# HeatBedRelay5D_int.net
KiCad netlist of a schematic drawn in EAGLE
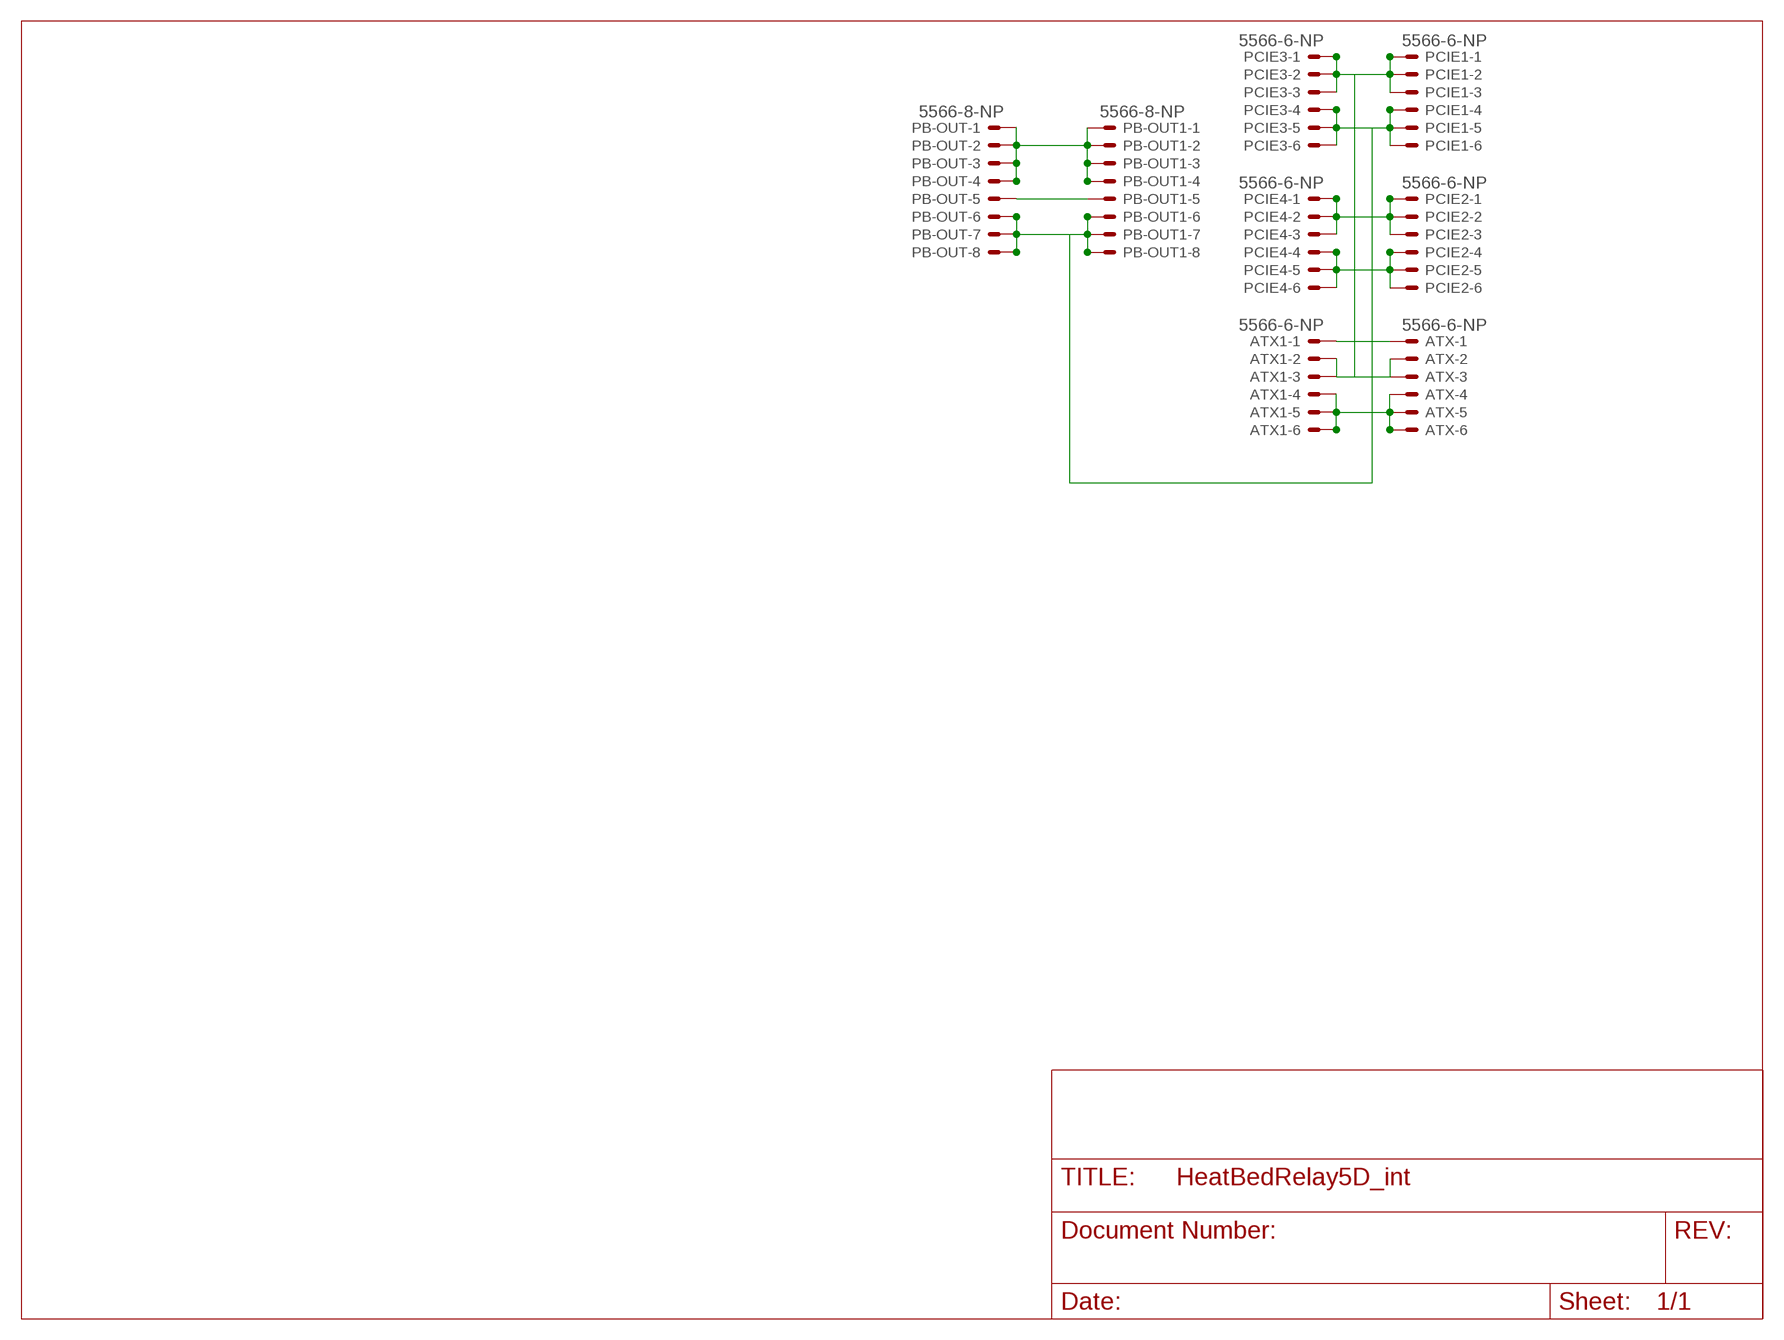
[diagram p0: schematic, sheet 1]

(export (version "E")
  (design (tool "Eeschema 10.0.6"))
  (components
    (comp (ref "ATX")
      (value "5566-6-NP")
      (footprint "eagle-import:5566-6-NP")
      (libsource (lib "eagle-import") (part "5566-6-NP"))
    )
    (comp (ref "ATX1")
      (value "5566-6-NP")
      (footprint "eagle-import:5566-6-NP")
      (libsource (lib "eagle-import") (part "5566-6-NP"))
    )
    (comp (ref "PB-OUT")
      (value "5566-8-NP")
      (footprint "eagle-import:5566-8-NP")
      (libsource (lib "eagle-import") (part "5566-8-NP"))
    )
    (comp (ref "PB-OUT1")
      (value "5566-8-NP")
      (footprint "eagle-import:5566-8-NP")
      (libsource (lib "eagle-import") (part "5566-8-NP"))
    )
    (comp (ref "PCIE1")
      (value "5566-6-NP")
      (footprint "eagle-import:5566-6-NP")
      (libsource (lib "eagle-import") (part "5566-6-NP"))
    )
    (comp (ref "PCIE2")
      (value "5566-6-NP")
      (footprint "eagle-import:5566-6-NP")
      (libsource (lib "eagle-import") (part "5566-6-NP"))
    )
    (comp (ref "PCIE3")
      (value "5566-6-NP")
      (footprint "eagle-import:5566-6-NP")
      (libsource (lib "eagle-import") (part "5566-6-NP"))
    )
    (comp (ref "PCIE4")
      (value "5566-6-NP")
      (footprint "eagle-import:5566-6-NP")
      (libsource (lib "eagle-import") (part "5566-6-NP"))
    )
  )
  (nets
    (net (code "1") (name "Net-(ATX1A-S)") (class "Default")
      (node (ref "ATX") (pin "1") (pinfunction "S_1") (pintype "passive"))
      (node (ref "ATX1") (pin "1") (pinfunction "S_1") (pintype "passive"))
    )
    (net (code "2") (name "Net-(ATX1B-S)") (class "Default")
      (node (ref "ATX") (pin "2") (pinfunction "S_2") (pintype "passive"))
      (node (ref "ATX") (pin "3") (pinfunction "S_3") (pintype "passive"))
      (node (ref "ATX1") (pin "2") (pinfunction "S_2") (pintype "passive"))
      (node (ref "ATX1") (pin "3") (pinfunction "S_3") (pintype "passive"))
      (node (ref "PCIE1") (pin "1") (pinfunction "S_1") (pintype "passive"))
      (node (ref "PCIE1") (pin "2") (pinfunction "S_2") (pintype "passive"))
      (node (ref "PCIE1") (pin "3") (pinfunction "S_3") (pintype "passive"))
      (node (ref "PCIE2") (pin "1") (pinfunction "S_1") (pintype "passive"))
      (node (ref "PCIE2") (pin "2") (pinfunction "S_2") (pintype "passive"))
      (node (ref "PCIE2") (pin "3") (pinfunction "S_3") (pintype "passive"))
      (node (ref "PCIE3") (pin "1") (pinfunction "S_1") (pintype "passive"))
      (node (ref "PCIE3") (pin "2") (pinfunction "S_2") (pintype "passive"))
      (node (ref "PCIE3") (pin "3") (pinfunction "S_3") (pintype "passive"))
      (node (ref "PCIE4") (pin "1") (pinfunction "S_1") (pintype "passive"))
      (node (ref "PCIE4") (pin "2") (pinfunction "S_2") (pintype "passive"))
      (node (ref "PCIE4") (pin "3") (pinfunction "S_3") (pintype "passive"))
    )
    (net (code "3") (name "Net-(ATX1D-S)") (class "Default")
      (node (ref "ATX") (pin "4") (pinfunction "S_4") (pintype "passive"))
      (node (ref "ATX") (pin "5") (pinfunction "S_5") (pintype "passive"))
      (node (ref "ATX") (pin "6") (pinfunction "S_6") (pintype "passive"))
      (node (ref "ATX1") (pin "4") (pinfunction "S_4") (pintype "passive"))
      (node (ref "ATX1") (pin "5") (pinfunction "S_5") (pintype "passive"))
      (node (ref "ATX1") (pin "6") (pinfunction "S_6") (pintype "passive"))
      (node (ref "PB-OUT") (pin "6") (pinfunction "S_6") (pintype "passive"))
      (node (ref "PB-OUT") (pin "7") (pinfunction "S_7") (pintype "passive"))
      (node (ref "PB-OUT") (pin "8") (pinfunction "S_8") (pintype "passive"))
      (node (ref "PB-OUT1") (pin "6") (pinfunction "S_6") (pintype "passive"))
      (node (ref "PB-OUT1") (pin "7") (pinfunction "S_7") (pintype "passive"))
      (node (ref "PB-OUT1") (pin "8") (pinfunction "S_8") (pintype "passive"))
      (node (ref "PCIE1") (pin "4") (pinfunction "S_4") (pintype "passive"))
      (node (ref "PCIE1") (pin "5") (pinfunction "S_5") (pintype "passive"))
      (node (ref "PCIE1") (pin "6") (pinfunction "S_6") (pintype "passive"))
      (node (ref "PCIE2") (pin "4") (pinfunction "S_4") (pintype "passive"))
      (node (ref "PCIE2") (pin "5") (pinfunction "S_5") (pintype "passive"))
      (node (ref "PCIE2") (pin "6") (pinfunction "S_6") (pintype "passive"))
      (node (ref "PCIE3") (pin "4") (pinfunction "S_4") (pintype "passive"))
      (node (ref "PCIE3") (pin "5") (pinfunction "S_5") (pintype "passive"))
      (node (ref "PCIE3") (pin "6") (pinfunction "S_6") (pintype "passive"))
      (node (ref "PCIE4") (pin "4") (pinfunction "S_4") (pintype "passive"))
      (node (ref "PCIE4") (pin "5") (pinfunction "S_5") (pintype "passive"))
      (node (ref "PCIE4") (pin "6") (pinfunction "S_6") (pintype "passive"))
    )
    (net (code "4") (name "Net-(PB-OUT1A-S)") (class "Default")
      (node (ref "PB-OUT") (pin "1") (pinfunction "S_1") (pintype "passive"))
      (node (ref "PB-OUT") (pin "2") (pinfunction "S_2") (pintype "passive"))
      (node (ref "PB-OUT") (pin "3") (pinfunction "S_3") (pintype "passive"))
      (node (ref "PB-OUT") (pin "4") (pinfunction "S_4") (pintype "passive"))
      (node (ref "PB-OUT1") (pin "1") (pinfunction "S_1") (pintype "passive"))
      (node (ref "PB-OUT1") (pin "2") (pinfunction "S_2") (pintype "passive"))
      (node (ref "PB-OUT1") (pin "3") (pinfunction "S_3") (pintype "passive"))
      (node (ref "PB-OUT1") (pin "4") (pinfunction "S_4") (pintype "passive"))
    )
    (net (code "5") (name "Net-(PB-OUT1E-S)") (class "Default")
      (node (ref "PB-OUT") (pin "5") (pinfunction "S_5") (pintype "passive"))
      (node (ref "PB-OUT1") (pin "5") (pinfunction "S_5") (pintype "passive"))
    )
  )
)
